# can4vscp_eth_rev_A.net
KiCad netlist of a schematic drawn in EAGLE
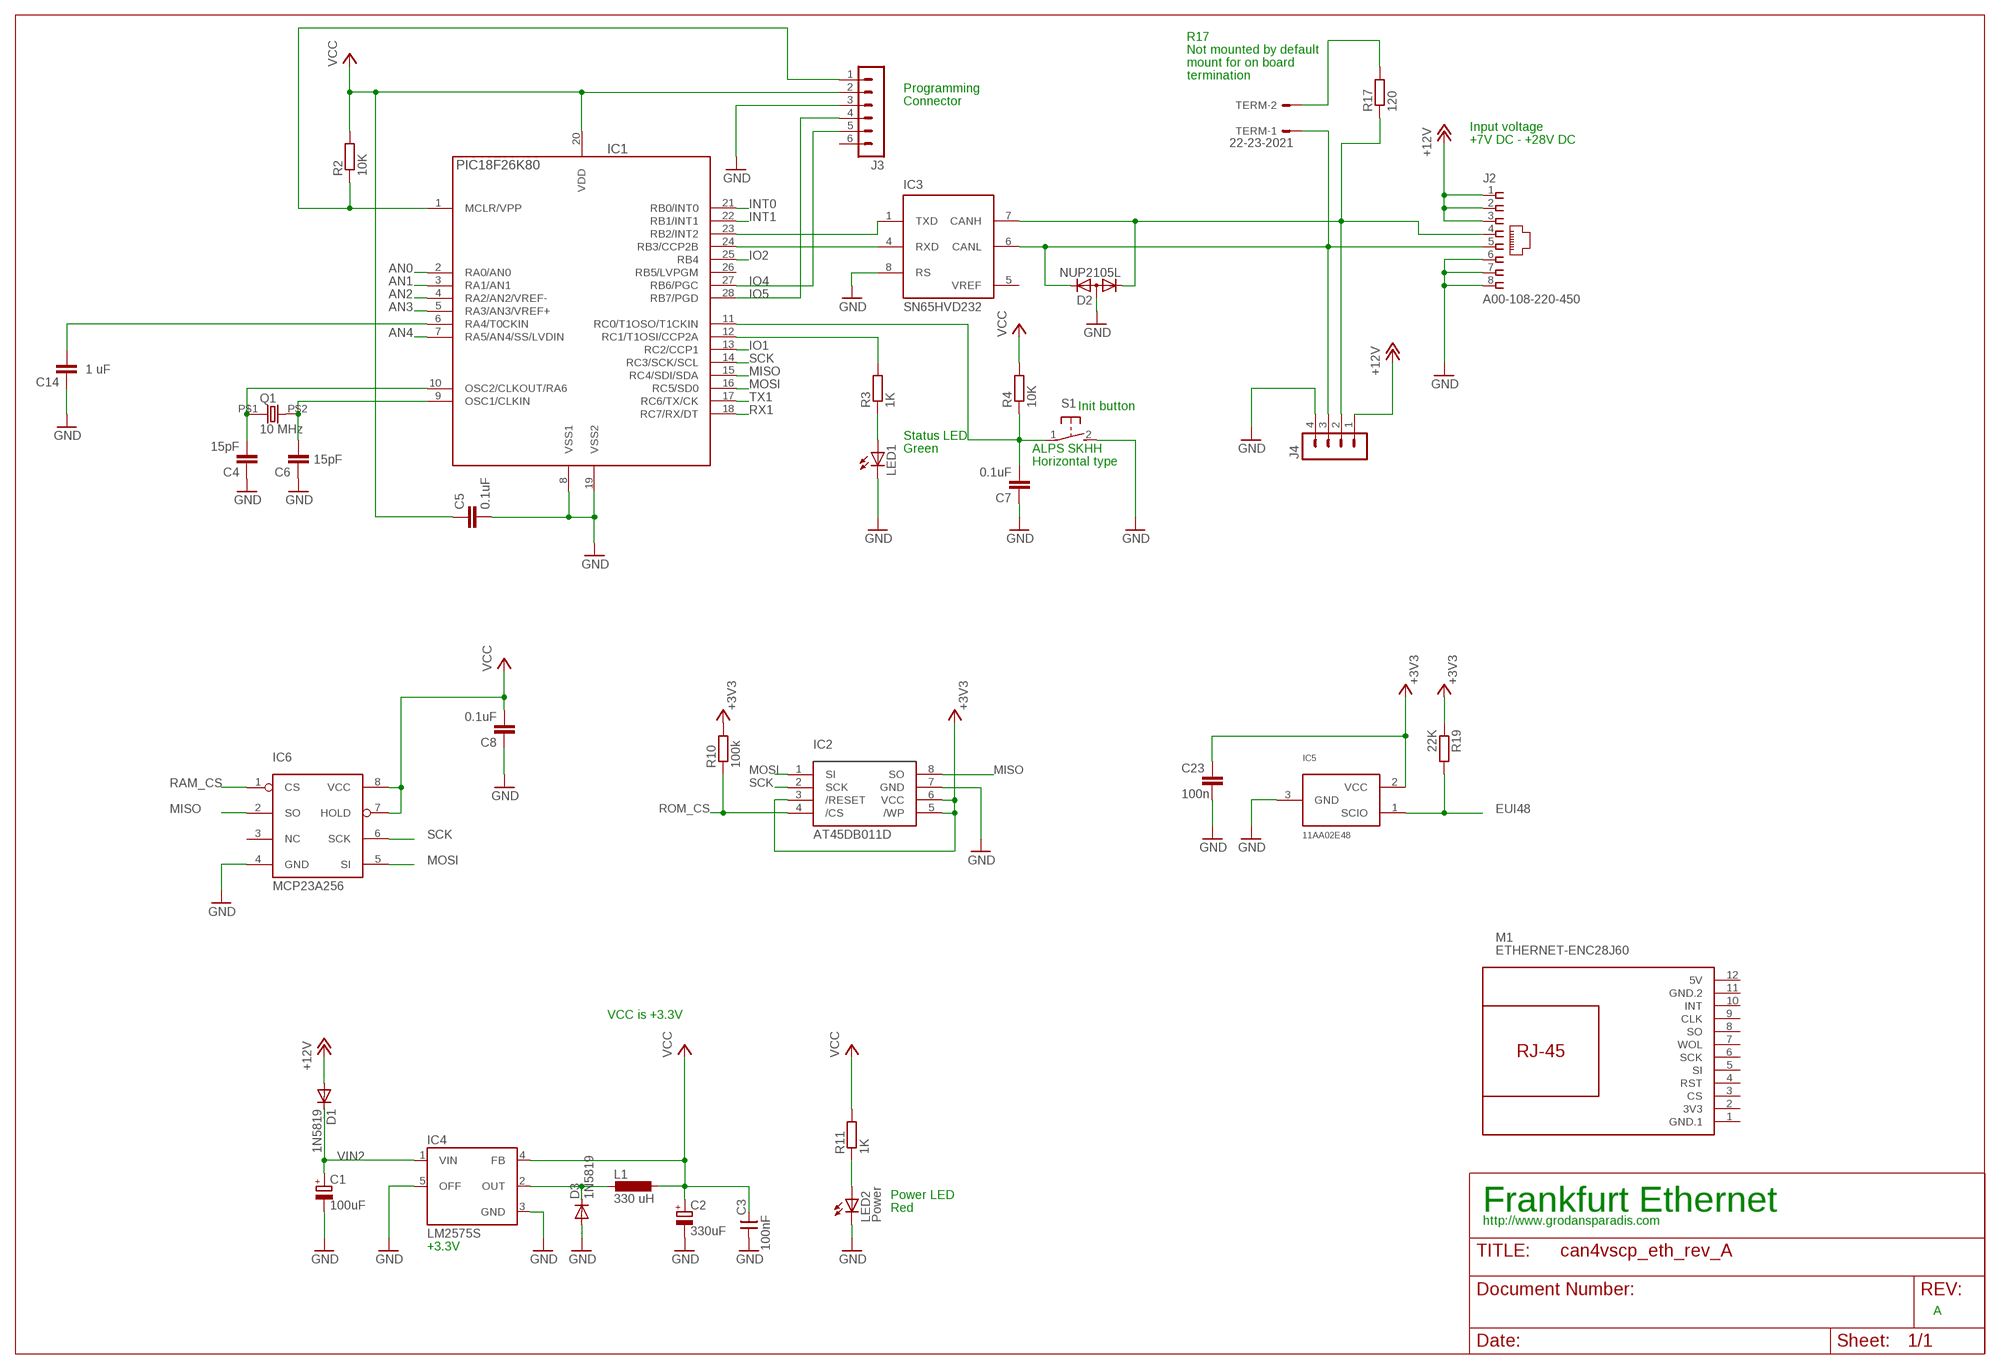
[diagram p0: schematic, sheet 1]

(export (version "E")
  (design (tool "Eeschema 10.0.6"))
  (components
    (comp (ref "C1")
      (value "100uF")
      (footprint "eagle-import:PANASONIC_D")
      (libsource (lib "eagle-import") (part "CPOL-EUD"))
    )
    (comp (ref "C2")
      (value "330uF")
      (footprint "eagle-import:PANASONIC_D")
      (libsource (lib "eagle-import") (part "CPOL-EUD"))
    )
    (comp (ref "C3")
      (value "100nF")
      (footprint "eagle-import:0805")
      (libsource (lib "eagle-import") (part "CNP-0805"))
    )
    (comp (ref "C4")
      (value "15pF")
      (footprint "eagle-import:C0805")
      (libsource (lib "eagle-import") (part "C-EUC0805"))
    )
    (comp (ref "C5")
      (value "0.1uF")
      (footprint "eagle-import:C0805")
      (libsource (lib "eagle-import") (part "C-EUC0805"))
    )
    (comp (ref "C6")
      (value "15pF")
      (footprint "eagle-import:C0805")
      (libsource (lib "eagle-import") (part "C-EUC0805"))
    )
    (comp (ref "C7")
      (value "0.1uF")
      (footprint "eagle-import:C0805")
      (libsource (lib "eagle-import") (part "C-EUC0805"))
    )
    (comp (ref "C8")
      (value "0.1uF")
      (footprint "eagle-import:C0805")
      (libsource (lib "eagle-import") (part "C-EUC0805"))
    )
    (comp (ref "C14")
      (value "1 uF")
      (footprint "eagle-import:C0805")
      (libsource (lib "eagle-import") (part "C-EUC0805"))
    )
    (comp (ref "C23")
      (value "100n")
      (footprint "eagle-import:C0805")
      (libsource (lib "eagle-import") (part "C-EUC0805"))
    )
    (comp (ref "D1")
      (value "1N5819")
      (footprint "eagle-import:SOD123")
      (libsource (lib "eagle-import") (part "DIODE-SOD123"))
    )
    (comp (ref "D2")
      (value "NUP2105L")
      (footprint "eagle-import:SOT23")
      (libsource (lib "eagle-import") (part "DIODE-2CA|ACSOT23"))
    )
    (comp (ref "D3")
      (value "1N5819")
      (footprint "eagle-import:SOD123")
      (libsource (lib "eagle-import") (part "DIODE-SOD123"))
    )
    (comp (ref "IC1")
      (value "PIC18F26K80")
      (footprint "eagle-import:SO28")
      (libsource (lib "eagle-import") (part "PIC18F252-?I/SOL"))
    )
    (comp (ref "IC2")
      (value "AT45DB011D")
      (footprint "eagle-import:SOP8W")
      (libsource (lib "eagle-import") (part "AT45DB011DSOP8W"))
    )
    (comp (ref "IC3")
      (value "SN65HVD232")
      (footprint "eagle-import:SO-08")
      (libsource (lib "eagle-import") (part "MCP2551SN"))
    )
    (comp (ref "IC4")
      (value "LM2575S")
      (footprint "eagle-import:TO263-5")
      (libsource (lib "eagle-import") (part "LM2575S"))
    )
    (comp (ref "IC5")
      (value "11AA02E48")
      (footprint "eagle-import:SOT23")
      (libsource (lib "eagle-import") (part "11AA02E48"))
    )
    (comp (ref "IC6")
      (value "MCP23A256")
      (footprint "eagle-import:SO-8")
      (libsource (lib "eagle-import") (part "MCP23A256"))
    )
    (comp (ref "J2")
      (value "A00-108-220-450")
      (footprint "eagle-import:RJ-45")
      (libsource (lib "eagle-import") (part "A00-108-220-450"))
    )
    (comp (ref "J3")
      (value "MA06-1")
      (footprint "eagle-import:MA06-1")
      (libsource (lib "eagle-import") (part "MA06-1"))
    )
    (comp (ref "J4")
      (value "MA04-1")
      (footprint "eagle-import:MA04-1")
      (libsource (lib "eagle-import") (part "MA04-1"))
    )
    (comp (ref "L1")
      (value "330 uH")
      (footprint "eagle-import:DO3316P")
      (libsource (lib "eagle-import") (part "DO3316P"))
    )
    (comp (ref "LED1")
      (value "LEDCHIP-LED0805")
      (footprint "eagle-import:CHIP-LED0805")
      (libsource (lib "eagle-import") (part "LEDCHIP-LED0805"))
    )
    (comp (ref "LED2")
      (value "Power")
      (footprint "eagle-import:CHIP-LED0805")
      (libsource (lib "eagle-import") (part "LEDCHIP-LED0805"))
    )
    (comp (ref "M1")
      (value "ETHERNET-ENC28J60")
      (footprint "eagle-import:ETHERNET-ENC28J60")
      (libsource (lib "eagle-import") (part "ETHERNET-ENC28J60"))
    )
    (comp (ref "Q1")
      (value "10 MHz")
      (footprint "eagle-import:9C")
      (libsource (lib "eagle-import") (part "HC-49S"))
    )
    (comp (ref "R2")
      (value "10K")
      (footprint "eagle-import:R0805")
      (libsource (lib "eagle-import") (part "R-EU_R0805"))
    )
    (comp (ref "R3")
      (value "1K")
      (footprint "eagle-import:R0805")
      (libsource (lib "eagle-import") (part "R-EU_R0805"))
    )
    (comp (ref "R4")
      (value "10K")
      (footprint "eagle-import:R0805")
      (libsource (lib "eagle-import") (part "R-EU_R0805"))
    )
    (comp (ref "R10")
      (value "100k")
      (footprint "eagle-import:M0805")
      (libsource (lib "eagle-import") (part "R-EU_M0805"))
    )
    (comp (ref "R11")
      (value "1K")
      (footprint "eagle-import:R0805")
      (libsource (lib "eagle-import") (part "R-EU_R0805"))
    )
    (comp (ref "R17")
      (value "120")
      (footprint "eagle-import:R0805")
      (libsource (lib "eagle-import") (part "R-EU_R0805"))
    )
    (comp (ref "R19")
      (value "22K")
      (footprint "eagle-import:M0805")
      (libsource (lib "eagle-import") (part "R-EU_M0805"))
    )
    (comp (ref "S1")
      (value "31-XX")
      (footprint "eagle-import:B3F-31XX")
      (fields (field (name "MPN") "B3F-3100"))
      (libsource (lib "eagle-import") (part "31-XX"))
    )
    (comp (ref "TERM")
      (value "22-23-2021")
      (footprint "eagle-import:22-23-2021")
      (fields (field (name "MF") "MOLEX"))
      (libsource (lib "eagle-import") (part "22-23-2021"))
    )
  )
  (nets
    (net (code "1") (name "+3V3") (class "Default")
      (node (ref "C23") (pin "1") (pinfunction "1_1") (pintype "passive"))
      (node (ref "IC2") (pin "3") (pinfunction "/RESET_3") (pintype "input"))
      (node (ref "IC2") (pin "5") (pinfunction "/WP_5") (pintype "input"))
      (node (ref "IC2") (pin "6") (pinfunction "VCC_6") (pintype "power_in"))
      (node (ref "IC5") (pin "2") (pinfunction "VCC_2") (pintype "power_in"))
      (node (ref "R10") (pin "2") (pinfunction "2_2") (pintype "passive"))
      (node (ref "R19") (pin "1") (pinfunction "1_1") (pintype "passive"))
    )
    (net (code "2") (name "+12V") (class "Default")
      (node (ref "D1") (pin "A") (pinfunction "A_A") (pintype "passive"))
      (node (ref "J2") (pin "1") (pinfunction "1_1") (pintype "passive"))
      (node (ref "J2") (pin "2") (pinfunction "2_2") (pintype "passive"))
      (node (ref "J2") (pin "3") (pinfunction "3_3") (pintype "passive"))
      (node (ref "J4") (pin "1") (pinfunction "1_1") (pintype "passive"))
    )
    (net (code "3") (name "/3V3") (class "Default")
      (node (ref "M1") (pin "2") (pinfunction "3V3_2") (pintype "power_in"))
    )
    (net (code "4") (name "/5V") (class "Default")
      (node (ref "M1") (pin "12") (pinfunction "5V_12") (pintype "power_in"))
    )
    (net (code "5") (name "/AN0") (class "Default")
      (node (ref "IC1") (pin "2") (pinfunction "RA0/AN0_2") (pintype "bidirectional"))
    )
    (net (code "6") (name "/AN1") (class "Default")
      (node (ref "IC1") (pin "3") (pinfunction "RA1/AN1_3") (pintype "bidirectional"))
    )
    (net (code "7") (name "/AN2") (class "Default")
      (node (ref "IC1") (pin "4") (pinfunction "RA2/AN2/VREF-_4") (pintype "bidirectional"))
    )
    (net (code "8") (name "/AN3") (class "Default")
      (node (ref "IC1") (pin "5") (pinfunction "RA3/AN3/VREF+_5") (pintype "bidirectional"))
    )
    (net (code "9") (name "/AN4") (class "Default")
      (node (ref "IC1") (pin "7") (pinfunction "RA5/AN4/SS/LVDIN_7") (pintype "bidirectional"))
    )
    (net (code "10") (name "/EUI48") (class "Default")
      (node (ref "IC5") (pin "1") (pinfunction "SCIO_1") (pintype "bidirectional"))
      (node (ref "R19") (pin "2") (pinfunction "2_2") (pintype "passive"))
    )
    (net (code "11") (name "/GND.1") (class "Default")
      (node (ref "M1") (pin "1") (pinfunction "GND.1_1") (pintype "power_in"))
    )
    (net (code "12") (name "/GND.2") (class "Default")
      (node (ref "M1") (pin "11") (pinfunction "GND.2_11") (pintype "power_in"))
    )
    (net (code "13") (name "/INT0") (class "Default")
      (node (ref "IC1") (pin "21") (pinfunction "RB0/INT0_21") (pintype "bidirectional"))
    )
    (net (code "14") (name "/INT1") (class "Default")
      (node (ref "IC1") (pin "22") (pinfunction "RB1/INT1_22") (pintype "bidirectional"))
    )
    (net (code "15") (name "/IO1") (class "Default")
      (node (ref "IC1") (pin "13") (pinfunction "RC2/CCP1_13") (pintype "bidirectional"))
    )
    (net (code "16") (name "/IO2") (class "Default")
      (node (ref "IC1") (pin "25") (pinfunction "RB4_25") (pintype "bidirectional"))
    )
    (net (code "17") (name "/IO4") (class "Default")
      (node (ref "IC1") (pin "27") (pinfunction "RB6/PGC_27") (pintype "bidirectional"))
      (node (ref "J3") (pin "5") (pinfunction "5_5") (pintype "passive"))
    )
    (net (code "18") (name "/IO5") (class "Default")
      (node (ref "IC1") (pin "28") (pinfunction "RB7/PGD_28") (pintype "bidirectional"))
      (node (ref "J3") (pin "4") (pinfunction "4_4") (pintype "passive"))
    )
    (net (code "19") (name "/MISO") (class "Default")
      (node (ref "IC1") (pin "15") (pinfunction "RC4/SDI/SDA_15") (pintype "bidirectional"))
      (node (ref "IC2") (pin "8") (pinfunction "SO_8") (pintype "output"))
      (node (ref "IC6") (pin "2") (pinfunction "SO_2") (pintype "output"))
    )
    (net (code "20") (name "/MOSI") (class "Default")
      (node (ref "IC1") (pin "16") (pinfunction "RC5/SD0_16") (pintype "bidirectional"))
      (node (ref "IC2") (pin "1") (pinfunction "SI_1") (pintype "input"))
      (node (ref "IC6") (pin "5") (pinfunction "SI_5") (pintype "input"))
    )
    (net (code "21") (name "/RAM_CS") (class "Default")
      (node (ref "IC6") (pin "1") (pinfunction "CS_1") (pintype "input"))
    )
    (net (code "22") (name "/ROM_CS") (class "Default")
      (node (ref "IC2") (pin "4") (pinfunction "/CS_4") (pintype "input"))
      (node (ref "R10") (pin "1") (pinfunction "1_1") (pintype "passive"))
    )
    (net (code "23") (name "/RX1") (class "Default")
      (node (ref "IC1") (pin "18") (pinfunction "RC7/RX/DT_18") (pintype "bidirectional"))
    )
    (net (code "24") (name "/SCK") (class "Default")
      (node (ref "IC1") (pin "14") (pinfunction "RC3/SCK/SCL_14") (pintype "bidirectional"))
      (node (ref "IC2") (pin "2") (pinfunction "SCK_2") (pintype "input"))
      (node (ref "IC6") (pin "6") (pinfunction "SCK_6") (pintype "input"))
    )
    (net (code "25") (name "/TX1") (class "Default")
      (node (ref "IC1") (pin "17") (pinfunction "RC6/TX/CK_17") (pintype "bidirectional"))
    )
    (net (code "26") (name "/VIN2") (class "Default")
      (node (ref "C1") (pin "+") (pinfunction "+_+") (pintype "passive"))
      (node (ref "D1") (pin "C") (pinfunction "C_C") (pintype "passive"))
      (node (ref "IC4") (pin "1") (pinfunction "VIN_1") (pintype "power_in"))
    )
    (net (code "27") (name "/VREF") (class "Default")
      (node (ref "IC3") (pin "5") (pinfunction "VREF_5") (pintype "power_in"))
    )
    (net (code "28") (name "GND") (class "Default")
      (node (ref "C1") (pin "-") (pinfunction "-_-") (pintype "passive"))
      (node (ref "C14") (pin "1") (pinfunction "1_1") (pintype "passive"))
      (node (ref "C2") (pin "-") (pinfunction "-_-") (pintype "passive"))
      (node (ref "C23") (pin "2") (pinfunction "2_2") (pintype "passive"))
      (node (ref "C3") (pin "1") (pinfunction "1_1") (pintype "passive"))
      (node (ref "C4") (pin "1") (pinfunction "1_1") (pintype "passive"))
      (node (ref "C5") (pin "2") (pinfunction "2_2") (pintype "passive"))
      (node (ref "C6") (pin "1") (pinfunction "1_1") (pintype "passive"))
      (node (ref "C7") (pin "1") (pinfunction "1_1") (pintype "passive"))
      (node (ref "C8") (pin "1") (pinfunction "1_1") (pintype "passive"))
      (node (ref "D2") (pin "3") (pinfunction "A_3") (pintype "passive"))
      (node (ref "D3") (pin "A") (pinfunction "A_A") (pintype "passive"))
      (node (ref "IC1") (pin "19") (pinfunction "VSS2_19") (pintype "power_in"))
      (node (ref "IC1") (pin "8") (pinfunction "VSS1_8") (pintype "power_in"))
      (node (ref "IC2") (pin "7") (pinfunction "GND_7") (pintype "power_in"))
      (node (ref "IC3") (pin "8") (pinfunction "RS_8") (pintype "input"))
      (node (ref "IC4") (pin "3") (pinfunction "GND_3") (pintype "power_in"))
      (node (ref "IC4") (pin "5") (pinfunction "OFF_5") (pintype "input"))
      (node (ref "IC5") (pin "3") (pinfunction "GND_3") (pintype "power_in"))
      (node (ref "IC6") (pin "4") (pinfunction "GND_4") (pintype "power_in"))
      (node (ref "J2") (pin "6") (pinfunction "6_6") (pintype "passive"))
      (node (ref "J2") (pin "7") (pinfunction "7_7") (pintype "passive"))
      (node (ref "J2") (pin "8") (pinfunction "8_8") (pintype "passive"))
      (node (ref "J3") (pin "3") (pinfunction "3_3") (pintype "passive"))
      (node (ref "J4") (pin "4") (pinfunction "4_4") (pintype "passive"))
      (node (ref "LED1") (pin "C") (pinfunction "C_C") (pintype "passive"))
      (node (ref "LED2") (pin "C") (pinfunction "C_C") (pintype "passive"))
      (node (ref "S1") (pin "2") (pinfunction "S_2") (pintype "passive"))
    )
    (net (code "29") (name "Net-(D2-K1)") (class "Default")
      (node (ref "D2") (pin "1") (pinfunction "K1_1") (pintype "passive"))
      (node (ref "IC3") (pin "7") (pinfunction "CANH_7") (pintype "bidirectional"))
      (node (ref "J2") (pin "4") (pinfunction "4_4") (pintype "passive"))
      (node (ref "J4") (pin "2") (pinfunction "2_2") (pintype "passive"))
      (node (ref "R17") (pin "1") (pinfunction "1_1") (pintype "passive"))
    )
    (net (code "30") (name "Net-(D2-K2)") (class "Default")
      (node (ref "D2") (pin "2") (pinfunction "K2_2") (pintype "passive"))
      (node (ref "IC3") (pin "6") (pinfunction "CANL_6") (pintype "bidirectional"))
      (node (ref "J2") (pin "5") (pinfunction "5_5") (pintype "passive"))
      (node (ref "J4") (pin "3") (pinfunction "3_3") (pintype "passive"))
      (node (ref "TERM") (pin "1") (pinfunction "S_1") (pintype "passive"))
    )
    (net (code "31") (name "Net-(IC1-MCLR{slash}VPP)") (class "Default")
      (node (ref "IC1") (pin "1") (pinfunction "MCLR/VPP_1") (pintype "input"))
      (node (ref "J3") (pin "1") (pinfunction "1_1") (pintype "passive"))
      (node (ref "R2") (pin "1") (pinfunction "1_1") (pintype "passive"))
    )
    (net (code "32") (name "Net-(IC1-OSC1{slash}CLKIN)") (class "Default")
      (node (ref "C6") (pin "2") (pinfunction "2_2") (pintype "passive"))
      (node (ref "IC1") (pin "9") (pinfunction "OSC1/CLKIN_9") (pintype "input"))
      (node (ref "Q1") (pin "P$2") (pinfunction "2_P$2") (pintype "passive"))
    )
    (net (code "33") (name "Net-(IC1-OSC2{slash}CLKOUT{slash}RA6)") (class "Default")
      (node (ref "C4") (pin "2") (pinfunction "2_2") (pintype "passive"))
      (node (ref "IC1") (pin "10") (pinfunction "OSC2/CLKOUT/RA6_10") (pintype "output"))
      (node (ref "Q1") (pin "P$1") (pinfunction "1_P$1") (pintype "passive"))
    )
    (net (code "34") (name "Net-(IC1-RA4{slash}T0CKIN)") (class "Default")
      (node (ref "C14") (pin "2") (pinfunction "2_2") (pintype "passive"))
      (node (ref "IC1") (pin "6") (pinfunction "RA4/T0CKIN_6") (pintype "open_collector"))
    )
    (net (code "35") (name "Net-(IC1-RB2{slash}INT2)") (class "Default")
      (node (ref "IC1") (pin "23") (pinfunction "RB2/INT2_23") (pintype "bidirectional"))
      (node (ref "IC3") (pin "1") (pinfunction "TXD_1") (pintype "input"))
    )
    (net (code "36") (name "Net-(IC1-RB3{slash}CCP2B)") (class "Default")
      (node (ref "IC1") (pin "24") (pinfunction "RB3/CCP2B_24") (pintype "bidirectional"))
      (node (ref "IC3") (pin "4") (pinfunction "RXD_4") (pintype "output"))
    )
    (net (code "37") (name "Net-(IC1-RC0{slash}T1OSO{slash}T1CKIN)") (class "Default")
      (node (ref "C7") (pin "2") (pinfunction "2_2") (pintype "passive"))
      (node (ref "IC1") (pin "11") (pinfunction "RC0/T1OSO/T1CKIN_11") (pintype "bidirectional"))
      (node (ref "R4") (pin "1") (pinfunction "1_1") (pintype "passive"))
      (node (ref "S1") (pin "1") (pinfunction "P_1") (pintype "passive"))
    )
    (net (code "38") (name "Net-(IC1-RC1{slash}T1OSI{slash}CCP2A)") (class "Default")
      (node (ref "IC1") (pin "12") (pinfunction "RC1/T1OSI/CCP2A_12") (pintype "bidirectional"))
      (node (ref "R3") (pin "2") (pinfunction "2_2") (pintype "passive"))
    )
    (net (code "39") (name "Net-(IC4-OUT)") (class "Default")
      (node (ref "D3") (pin "C") (pinfunction "C_C") (pintype "passive"))
      (node (ref "IC4") (pin "2") (pinfunction "OUT_2") (pintype "output"))
      (node (ref "L1") (pin "1") (pinfunction "1_1") (pintype "passive"))
    )
    (net (code "40") (name "Net-(LED1-PadA)") (class "Default")
      (node (ref "LED1") (pin "A") (pinfunction "A_A") (pintype "passive"))
      (node (ref "R3") (pin "1") (pinfunction "1_1") (pintype "passive"))
    )
    (net (code "41") (name "Net-(LED2-PadA)") (class "Default")
      (node (ref "LED2") (pin "A") (pinfunction "A_A") (pintype "passive"))
      (node (ref "R11") (pin "1") (pinfunction "1_1") (pintype "passive"))
    )
    (net (code "42") (name "Net-(TERMB-S)") (class "Default")
      (node (ref "R17") (pin "2") (pinfunction "2_2") (pintype "passive"))
      (node (ref "TERM") (pin "2") (pinfunction "S_2") (pintype "passive"))
    )
    (net (code "43") (name "VCC") (class "Default")
      (node (ref "C2") (pin "+") (pinfunction "+_+") (pintype "passive"))
      (node (ref "C3") (pin "2") (pinfunction "2_2") (pintype "passive"))
      (node (ref "C5") (pin "1") (pinfunction "1_1") (pintype "passive"))
      (node (ref "C8") (pin "2") (pinfunction "2_2") (pintype "passive"))
      (node (ref "IC1") (pin "20") (pinfunction "VDD_20") (pintype "power_in"))
      (node (ref "IC4") (pin "4") (pinfunction "FB_4") (pintype "input"))
      (node (ref "IC6") (pin "7") (pinfunction "HOLD_7") (pintype "input"))
      (node (ref "IC6") (pin "8") (pinfunction "VCC_8") (pintype "power_in"))
      (node (ref "J3") (pin "2") (pinfunction "2_2") (pintype "passive"))
      (node (ref "L1") (pin "2") (pinfunction "2_2") (pintype "passive"))
      (node (ref "R11") (pin "2") (pinfunction "2_2") (pintype "passive"))
      (node (ref "R2") (pin "2") (pinfunction "2_2") (pintype "passive"))
      (node (ref "R4") (pin "2") (pinfunction "2_2") (pintype "passive"))
    )
    (net (code "44") (name "unconnected-(IC1-RB5{slash}LVPGM-Pad26)") (class "Default")
      (node (ref "IC1") (pin "26") (pinfunction "RB5/LVPGM_26") (pintype "bidirectional"))
    )
    (net (code "45") (name "unconnected-(IC6-NC-Pad3)") (class "Default")
      (node (ref "IC6") (pin "3") (pinfunction "NC_3") (pintype "no_connect"))
    )
    (net (code "46") (name "unconnected-(J3-Pad6)") (class "Default")
      (node (ref "J3") (pin "6") (pinfunction "6_6") (pintype "passive"))
    )
    (net (code "47") (name "unconnected-(M1-CLK-Pad9)") (class "Default")
      (node (ref "M1") (pin "9") (pinfunction "CLK_9") (pintype "bidirectional"))
    )
    (net (code "48") (name "unconnected-(M1-CS-Pad3)") (class "Default")
      (node (ref "M1") (pin "3") (pinfunction "CS_3") (pintype "bidirectional"))
    )
    (net (code "49") (name "unconnected-(M1-INT-Pad10)") (class "Default")
      (node (ref "M1") (pin "10") (pinfunction "INT_10") (pintype "bidirectional"))
    )
    (net (code "50") (name "unconnected-(M1-RST-Pad4)") (class "Default")
      (node (ref "M1") (pin "4") (pinfunction "RST_4") (pintype "bidirectional"))
    )
    (net (code "51") (name "unconnected-(M1-SCK-Pad6)") (class "Default")
      (node (ref "M1") (pin "6") (pinfunction "SCK_6") (pintype "bidirectional"))
    )
    (net (code "52") (name "unconnected-(M1-SI-Pad5)") (class "Default")
      (node (ref "M1") (pin "5") (pinfunction "SI_5") (pintype "bidirectional"))
    )
    (net (code "53") (name "unconnected-(M1-SO-Pad8)") (class "Default")
      (node (ref "M1") (pin "8") (pinfunction "SO_8") (pintype "bidirectional"))
    )
    (net (code "54") (name "unconnected-(M1-WOL-Pad7)") (class "Default")
      (node (ref "M1") (pin "7") (pinfunction "WOL_7") (pintype "bidirectional"))
    )
  )
)
